# main.net
KiCad netlist of a schematic drawn in EAGLE
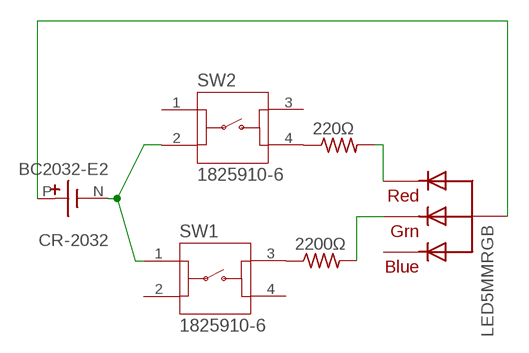
[diagram p0: schematic, sheet 1]

(export (version "E")
  (design (tool "Eeschema 10.0.6"))
  (components
    (comp (ref "220Ω")
      (value "R-US_0204/5")
      (footprint "eagle-import:0204_5")
      (libsource (lib "eagle-import") (part "R-US_0204/5"))
    )
    (comp (ref "2200Ω")
      (value "R-US_0204/5")
      (footprint "eagle-import:0204_5")
      (libsource (lib "eagle-import") (part "R-US_0204/5"))
    )
    (comp (ref "CR-2032")
      (value "BC2032-E2")
      (footprint "eagle-import:MPD_BC2032-E2")
      (fields (field (name "DIGI-KEY_PART_NUMBER") "BC2032-E2-ND") (field (name "MF") "MPD _Memory"))
      (libsource (lib "eagle-import") (part "BC2032-E2"))
    )
    (comp (ref "LED5MMRGB")
      (value "RGBLED_CA-5MM")
      (footprint "eagle-import:LED5MMRGB")
      (libsource (lib "eagle-import") (part "RGBLED_CA-5MM"))
    )
    (comp (ref "SW1")
      (value "1825910-6")
      (footprint "eagle-import:SW_1825910-6-4")
      (fields (field (name "DIGI-KEY_PART_NUMBER") "450-1650-ND") (field (name "MF") "TE Connectivity"))
      (libsource (lib "eagle-import") (part "1825910-6"))
    )
    (comp (ref "SW2")
      (value "1825910-6")
      (footprint "eagle-import:SW_1825910-6-4")
      (fields (field (name "DIGI-KEY_PART_NUMBER") "450-1650-ND") (field (name "MF") "TE Connectivity"))
      (libsource (lib "eagle-import") (part "1825910-6"))
    )
  )
  (nets
    (net (code "1") (name "Net-(220Ω-Pad1)") (class "Default")
      (node (ref "220Ω") (pin "1") (pinfunction "1_1") (pintype "passive"))
      (node (ref "SW2") (pin "4") (pinfunction "4_4") (pintype "passive"))
    )
    (net (code "2") (name "Net-(2200Ω-Pad1)") (class "Default")
      (node (ref "2200Ω") (pin "1") (pinfunction "1_1") (pintype "passive"))
      (node (ref "SW1") (pin "3") (pinfunction "3_3") (pintype "passive"))
    )
    (net (code "3") (name "Net-(CR-2032-PadN)") (class "Default")
      (node (ref "CR-2032") (pin "N") (pinfunction "N_N") (pintype "passive"))
      (node (ref "SW1") (pin "1") (pinfunction "1_1") (pintype "passive"))
      (node (ref "SW2") (pin "2") (pinfunction "2_2") (pintype "passive"))
    )
    (net (code "4") (name "Net-(LED5MMRGB-GREEN)") (class "Default")
      (node (ref "2200Ω") (pin "2") (pinfunction "2_2") (pintype "passive"))
      (node (ref "LED5MMRGB") (pin "3") (pinfunction "GREEN_3") (pintype "bidirectional"))
    )
    (net (code "5") (name "Net-(LED5MMRGB-RED)") (class "Default")
      (node (ref "220Ω") (pin "2") (pinfunction "2_2") (pintype "passive"))
      (node (ref "LED5MMRGB") (pin "1") (pinfunction "RED_1") (pintype "bidirectional"))
    )
    (net (code "6") (name "Net-(LED5MMRGB-VCC)") (class "Default")
      (node (ref "CR-2032") (pin "P") (pinfunction "P_P") (pintype "passive"))
      (node (ref "LED5MMRGB") (pin "2") (pinfunction "VCC_2") (pintype "bidirectional"))
    )
    (net (code "7") (name "unconnected-(LED5MMRGB-BLUE-Pad4)") (class "Default")
      (node (ref "LED5MMRGB") (pin "4") (pinfunction "BLUE_4") (pintype "bidirectional"))
    )
    (net (code "8") (name "unconnected-(SW1-Pad2)") (class "Default")
      (node (ref "SW1") (pin "2") (pinfunction "2_2") (pintype "passive"))
    )
    (net (code "9") (name "unconnected-(SW1-Pad4)") (class "Default")
      (node (ref "SW1") (pin "4") (pinfunction "4_4") (pintype "passive"))
    )
    (net (code "10") (name "unconnected-(SW2-Pad1)") (class "Default")
      (node (ref "SW2") (pin "1") (pinfunction "1_1") (pintype "passive"))
    )
    (net (code "11") (name "unconnected-(SW2-Pad3)") (class "Default")
      (node (ref "SW2") (pin "3") (pinfunction "3_3") (pintype "passive"))
    )
  )
)
